# 01.net
KiCad netlist of a schematic drawn in EAGLE
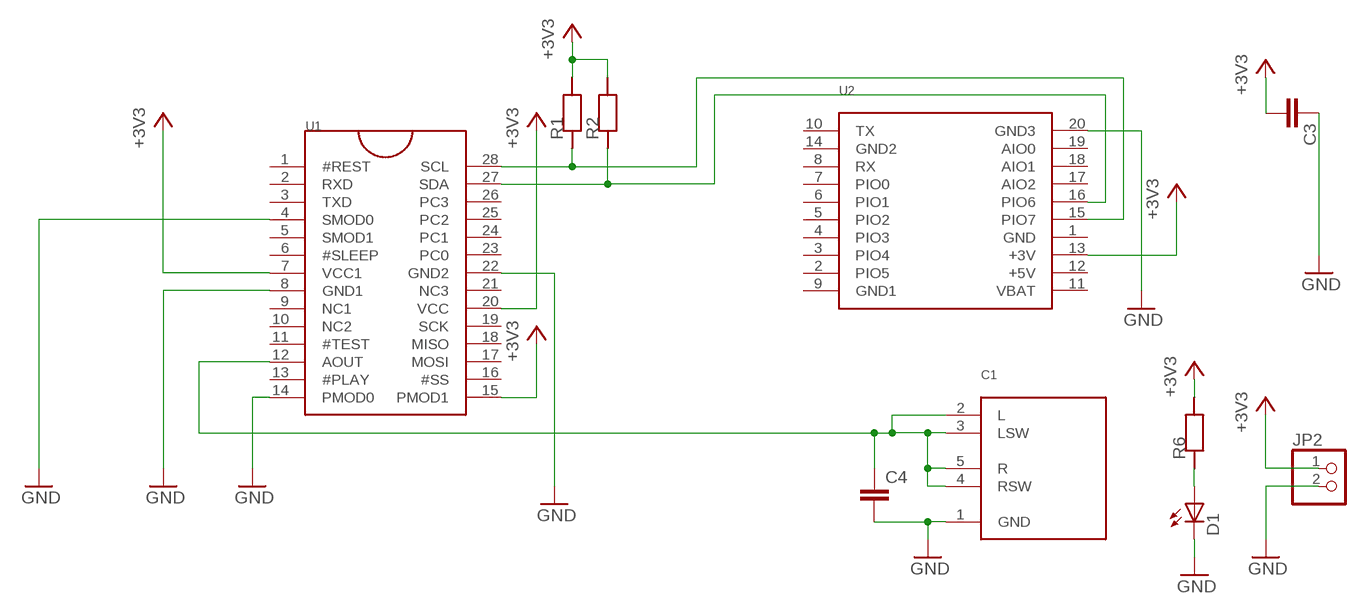
[diagram p0: schematic, sheet 1]

(export (version "E")
  (design (tool "Eeschema 10.0.6"))
  (components
    (comp (ref "C1")
      (value "C-02384_AJ-1780")
      (footprint "eagle-import:AJ-1780")
      (libsource (lib "eagle-import") (part "C-02384_AJ-1780"))
    )
    (comp (ref "C3")
      (value "C_1068")
      (footprint "eagle-import:C0603")
      (libsource (lib "eagle-import") (part "C_1068"))
    )
    (comp (ref "C4")
      (value "C_1068")
      (footprint "eagle-import:C0603")
      (libsource (lib "eagle-import") (part "C_1068"))
    )
    (comp (ref "D1")
      (value "LEDCHIPLED_0805")
      (footprint "eagle-import:CHIPLED_0805")
      (libsource (lib "eagle-import") (part "LEDCHIPLED_0805"))
    )
    (comp (ref "JP2")
      (value "PINHD-1X2/90")
      (footprint "eagle-import:1X02_90")
      (libsource (lib "eagle-import") (part "PINHD-1X2/90"))
    )
    (comp (ref "R1")
      (value "R_1068")
      (footprint "eagle-import:R0603")
      (libsource (lib "eagle-import") (part "R_1068"))
    )
    (comp (ref "R2")
      (value "R_1068")
      (footprint "eagle-import:R0603")
      (libsource (lib "eagle-import") (part "R_1068"))
    )
    (comp (ref "R6")
      (value "R_1068")
      (footprint "eagle-import:R0603")
      (libsource (lib "eagle-import") (part "R_1068"))
    )
    (comp (ref "U1")
      (value "I-06220_ATP3011F1-PU")
      (footprint "eagle-import:DIL28-3")
      (libsource (lib "eagle-import") (part "I-06220_ATP3011F1-PU"))
    )
    (comp (ref "U2")
      (value "KONASHI")
      (footprint "eagle-import:KONASHI")
      (libsource (lib "eagle-import") (part "KONASHI"))
    )
  )
  (nets
    (net (code "1") (name "+3V3") (class "Default")
      (node (ref "C3") (pin "2") (pinfunction "2_2") (pintype "passive"))
      (node (ref "JP2") (pin "1") (pinfunction "1_1") (pintype "passive"))
      (node (ref "R1") (pin "2") (pinfunction "2_2") (pintype "bidirectional"))
      (node (ref "R2") (pin "2") (pinfunction "2_2") (pintype "bidirectional"))
      (node (ref "R6") (pin "2") (pinfunction "2_2") (pintype "bidirectional"))
      (node (ref "U1") (pin "15") (pinfunction "PMOD1_15") (pintype "bidirectional"))
      (node (ref "U1") (pin "20") (pinfunction "VCC_20") (pintype "bidirectional"))
      (node (ref "U1") (pin "7") (pinfunction "VCC1_7") (pintype "bidirectional"))
      (node (ref "U2") (pin "13") (pinfunction "+3V_13") (pintype "bidirectional"))
    )
    (net (code "2") (name "GND") (class "Default")
      (node (ref "C1") (pin "1") (pinfunction "GND_1") (pintype "bidirectional"))
      (node (ref "C3") (pin "1") (pinfunction "1_1") (pintype "passive"))
      (node (ref "C4") (pin "2") (pinfunction "2_2") (pintype "passive"))
      (node (ref "D1") (pin "C") (pinfunction "C_C") (pintype "passive"))
      (node (ref "JP2") (pin "2") (pinfunction "2_2") (pintype "passive"))
      (node (ref "U1") (pin "14") (pinfunction "PMOD0_14") (pintype "bidirectional"))
      (node (ref "U1") (pin "22") (pinfunction "GND2_22") (pintype "bidirectional"))
      (node (ref "U1") (pin "4") (pinfunction "SMOD0_4") (pintype "bidirectional"))
      (node (ref "U1") (pin "8") (pinfunction "GND1_8") (pintype "bidirectional"))
      (node (ref "U2") (pin "20") (pinfunction "GND3_20") (pintype "bidirectional"))
    )
    (net (code "3") (name "Net-(C1-L)") (class "Default")
      (node (ref "C1") (pin "2") (pinfunction "L_2") (pintype "bidirectional"))
      (node (ref "C1") (pin "3") (pinfunction "LSW_3") (pintype "bidirectional"))
      (node (ref "C1") (pin "4") (pinfunction "RSW_4") (pintype "bidirectional"))
      (node (ref "C1") (pin "5") (pinfunction "R_5") (pintype "bidirectional"))
      (node (ref "C4") (pin "1") (pinfunction "1_1") (pintype "passive"))
      (node (ref "U1") (pin "12") (pinfunction "AOUT_12") (pintype "bidirectional"))
    )
    (net (code "4") (name "Net-(D1-PadA)") (class "Default")
      (node (ref "D1") (pin "A") (pinfunction "A_A") (pintype "passive"))
      (node (ref "R6") (pin "1") (pinfunction "1_1") (pintype "bidirectional"))
    )
    (net (code "5") (name "Net-(U1-SCL)") (class "Default")
      (node (ref "R1") (pin "1") (pinfunction "1_1") (pintype "bidirectional"))
      (node (ref "U1") (pin "28") (pinfunction "SCL_28") (pintype "bidirectional"))
      (node (ref "U2") (pin "15") (pinfunction "PIO7_15") (pintype "bidirectional"))
    )
    (net (code "6") (name "Net-(U1-SDA)") (class "Default")
      (node (ref "R2") (pin "1") (pinfunction "1_1") (pintype "bidirectional"))
      (node (ref "U1") (pin "27") (pinfunction "SDA_27") (pintype "bidirectional"))
      (node (ref "U2") (pin "16") (pinfunction "PIO6_16") (pintype "bidirectional"))
    )
    (net (code "7") (name "unconnected-(U1-#PLAY-Pad13)") (class "Default")
      (node (ref "U1") (pin "13") (pinfunction "#PLAY_13") (pintype "bidirectional"))
    )
    (net (code "8") (name "unconnected-(U1-#REST-Pad1)") (class "Default")
      (node (ref "U1") (pin "1") (pinfunction "#REST_1") (pintype "bidirectional"))
    )
    (net (code "9") (name "unconnected-(U1-#SLEEP-Pad6)") (class "Default")
      (node (ref "U1") (pin "6") (pinfunction "#SLEEP_6") (pintype "bidirectional"))
    )
    (net (code "10") (name "unconnected-(U1-#SS-Pad16)") (class "Default")
      (node (ref "U1") (pin "16") (pinfunction "#SS_16") (pintype "bidirectional"))
    )
    (net (code "11") (name "unconnected-(U1-#TEST-Pad11)") (class "Default")
      (node (ref "U1") (pin "11") (pinfunction "#TEST_11") (pintype "bidirectional"))
    )
    (net (code "12") (name "unconnected-(U1-MISO-Pad18)") (class "Default")
      (node (ref "U1") (pin "18") (pinfunction "MISO_18") (pintype "bidirectional"))
    )
    (net (code "13") (name "unconnected-(U1-MOSI-Pad17)") (class "Default")
      (node (ref "U1") (pin "17") (pinfunction "MOSI_17") (pintype "bidirectional"))
    )
    (net (code "14") (name "unconnected-(U1-NC1-Pad9)") (class "Default")
      (node (ref "U1") (pin "9") (pinfunction "NC1_9") (pintype "bidirectional"))
    )
    (net (code "15") (name "unconnected-(U1-NC2-Pad10)") (class "Default")
      (node (ref "U1") (pin "10") (pinfunction "NC2_10") (pintype "bidirectional"))
    )
    (net (code "16") (name "unconnected-(U1-NC3-Pad21)") (class "Default")
      (node (ref "U1") (pin "21") (pinfunction "NC3_21") (pintype "bidirectional"))
    )
    (net (code "17") (name "unconnected-(U1-PC0-Pad23)") (class "Default")
      (node (ref "U1") (pin "23") (pinfunction "PC0_23") (pintype "bidirectional"))
    )
    (net (code "18") (name "unconnected-(U1-PC1-Pad24)") (class "Default")
      (node (ref "U1") (pin "24") (pinfunction "PC1_24") (pintype "bidirectional"))
    )
    (net (code "19") (name "unconnected-(U1-PC2-Pad25)") (class "Default")
      (node (ref "U1") (pin "25") (pinfunction "PC2_25") (pintype "bidirectional"))
    )
    (net (code "20") (name "unconnected-(U1-PC3-Pad26)") (class "Default")
      (node (ref "U1") (pin "26") (pinfunction "PC3_26") (pintype "bidirectional"))
    )
    (net (code "21") (name "unconnected-(U1-RXD-Pad2)") (class "Default")
      (node (ref "U1") (pin "2") (pinfunction "RXD_2") (pintype "bidirectional"))
    )
    (net (code "22") (name "unconnected-(U1-SCK-Pad19)") (class "Default")
      (node (ref "U1") (pin "19") (pinfunction "SCK_19") (pintype "bidirectional"))
    )
    (net (code "23") (name "unconnected-(U1-SMOD1-Pad5)") (class "Default")
      (node (ref "U1") (pin "5") (pinfunction "SMOD1_5") (pintype "bidirectional"))
    )
    (net (code "24") (name "unconnected-(U1-TXD-Pad3)") (class "Default")
      (node (ref "U1") (pin "3") (pinfunction "TXD_3") (pintype "bidirectional"))
    )
    (net (code "25") (name "unconnected-(U2-+5V-Pad12)") (class "Default")
      (node (ref "U2") (pin "12") (pinfunction "+5V_12") (pintype "bidirectional"))
    )
    (net (code "26") (name "unconnected-(U2-AIO0-Pad19)") (class "Default")
      (node (ref "U2") (pin "19") (pinfunction "AIO0_19") (pintype "bidirectional"))
    )
    (net (code "27") (name "unconnected-(U2-AIO1-Pad18)") (class "Default")
      (node (ref "U2") (pin "18") (pinfunction "AIO1_18") (pintype "bidirectional"))
    )
    (net (code "28") (name "unconnected-(U2-AIO2-Pad17)") (class "Default")
      (node (ref "U2") (pin "17") (pinfunction "AIO2_17") (pintype "bidirectional"))
    )
    (net (code "29") (name "unconnected-(U2-GND-Pad1)") (class "Default")
      (node (ref "U2") (pin "1") (pinfunction "GND_1") (pintype "bidirectional"))
    )
    (net (code "30") (name "unconnected-(U2-GND1-Pad9)") (class "Default")
      (node (ref "U2") (pin "9") (pinfunction "GND1_9") (pintype "bidirectional"))
    )
    (net (code "31") (name "unconnected-(U2-GND2-Pad14)") (class "Default")
      (node (ref "U2") (pin "14") (pinfunction "GND2_14") (pintype "bidirectional"))
    )
    (net (code "32") (name "unconnected-(U2-PIO0-Pad7)") (class "Default")
      (node (ref "U2") (pin "7") (pinfunction "PIO0_7") (pintype "bidirectional"))
    )
    (net (code "33") (name "unconnected-(U2-PIO1-Pad6)") (class "Default")
      (node (ref "U2") (pin "6") (pinfunction "PIO1_6") (pintype "bidirectional"))
    )
    (net (code "34") (name "unconnected-(U2-PIO2-Pad5)") (class "Default")
      (node (ref "U2") (pin "5") (pinfunction "PIO2_5") (pintype "bidirectional"))
    )
    (net (code "35") (name "unconnected-(U2-PIO3-Pad4)") (class "Default")
      (node (ref "U2") (pin "4") (pinfunction "PIO3_4") (pintype "bidirectional"))
    )
    (net (code "36") (name "unconnected-(U2-PIO4-Pad3)") (class "Default")
      (node (ref "U2") (pin "3") (pinfunction "PIO4_3") (pintype "bidirectional"))
    )
    (net (code "37") (name "unconnected-(U2-PIO5-Pad2)") (class "Default")
      (node (ref "U2") (pin "2") (pinfunction "PIO5_2") (pintype "bidirectional"))
    )
    (net (code "38") (name "unconnected-(U2-RX-Pad8)") (class "Default")
      (node (ref "U2") (pin "8") (pinfunction "RX_8") (pintype "bidirectional"))
    )
    (net (code "39") (name "unconnected-(U2-TX-Pad10)") (class "Default")
      (node (ref "U2") (pin "10") (pinfunction "TX_10") (pintype "bidirectional"))
    )
    (net (code "40") (name "unconnected-(U2-VBAT-Pad11)") (class "Default")
      (node (ref "U2") (pin "11") (pinfunction "VBAT_11") (pintype "bidirectional"))
    )
  )
)
